# audio_out.net
KiCad netlist of a schematic drawn in Altium Designer
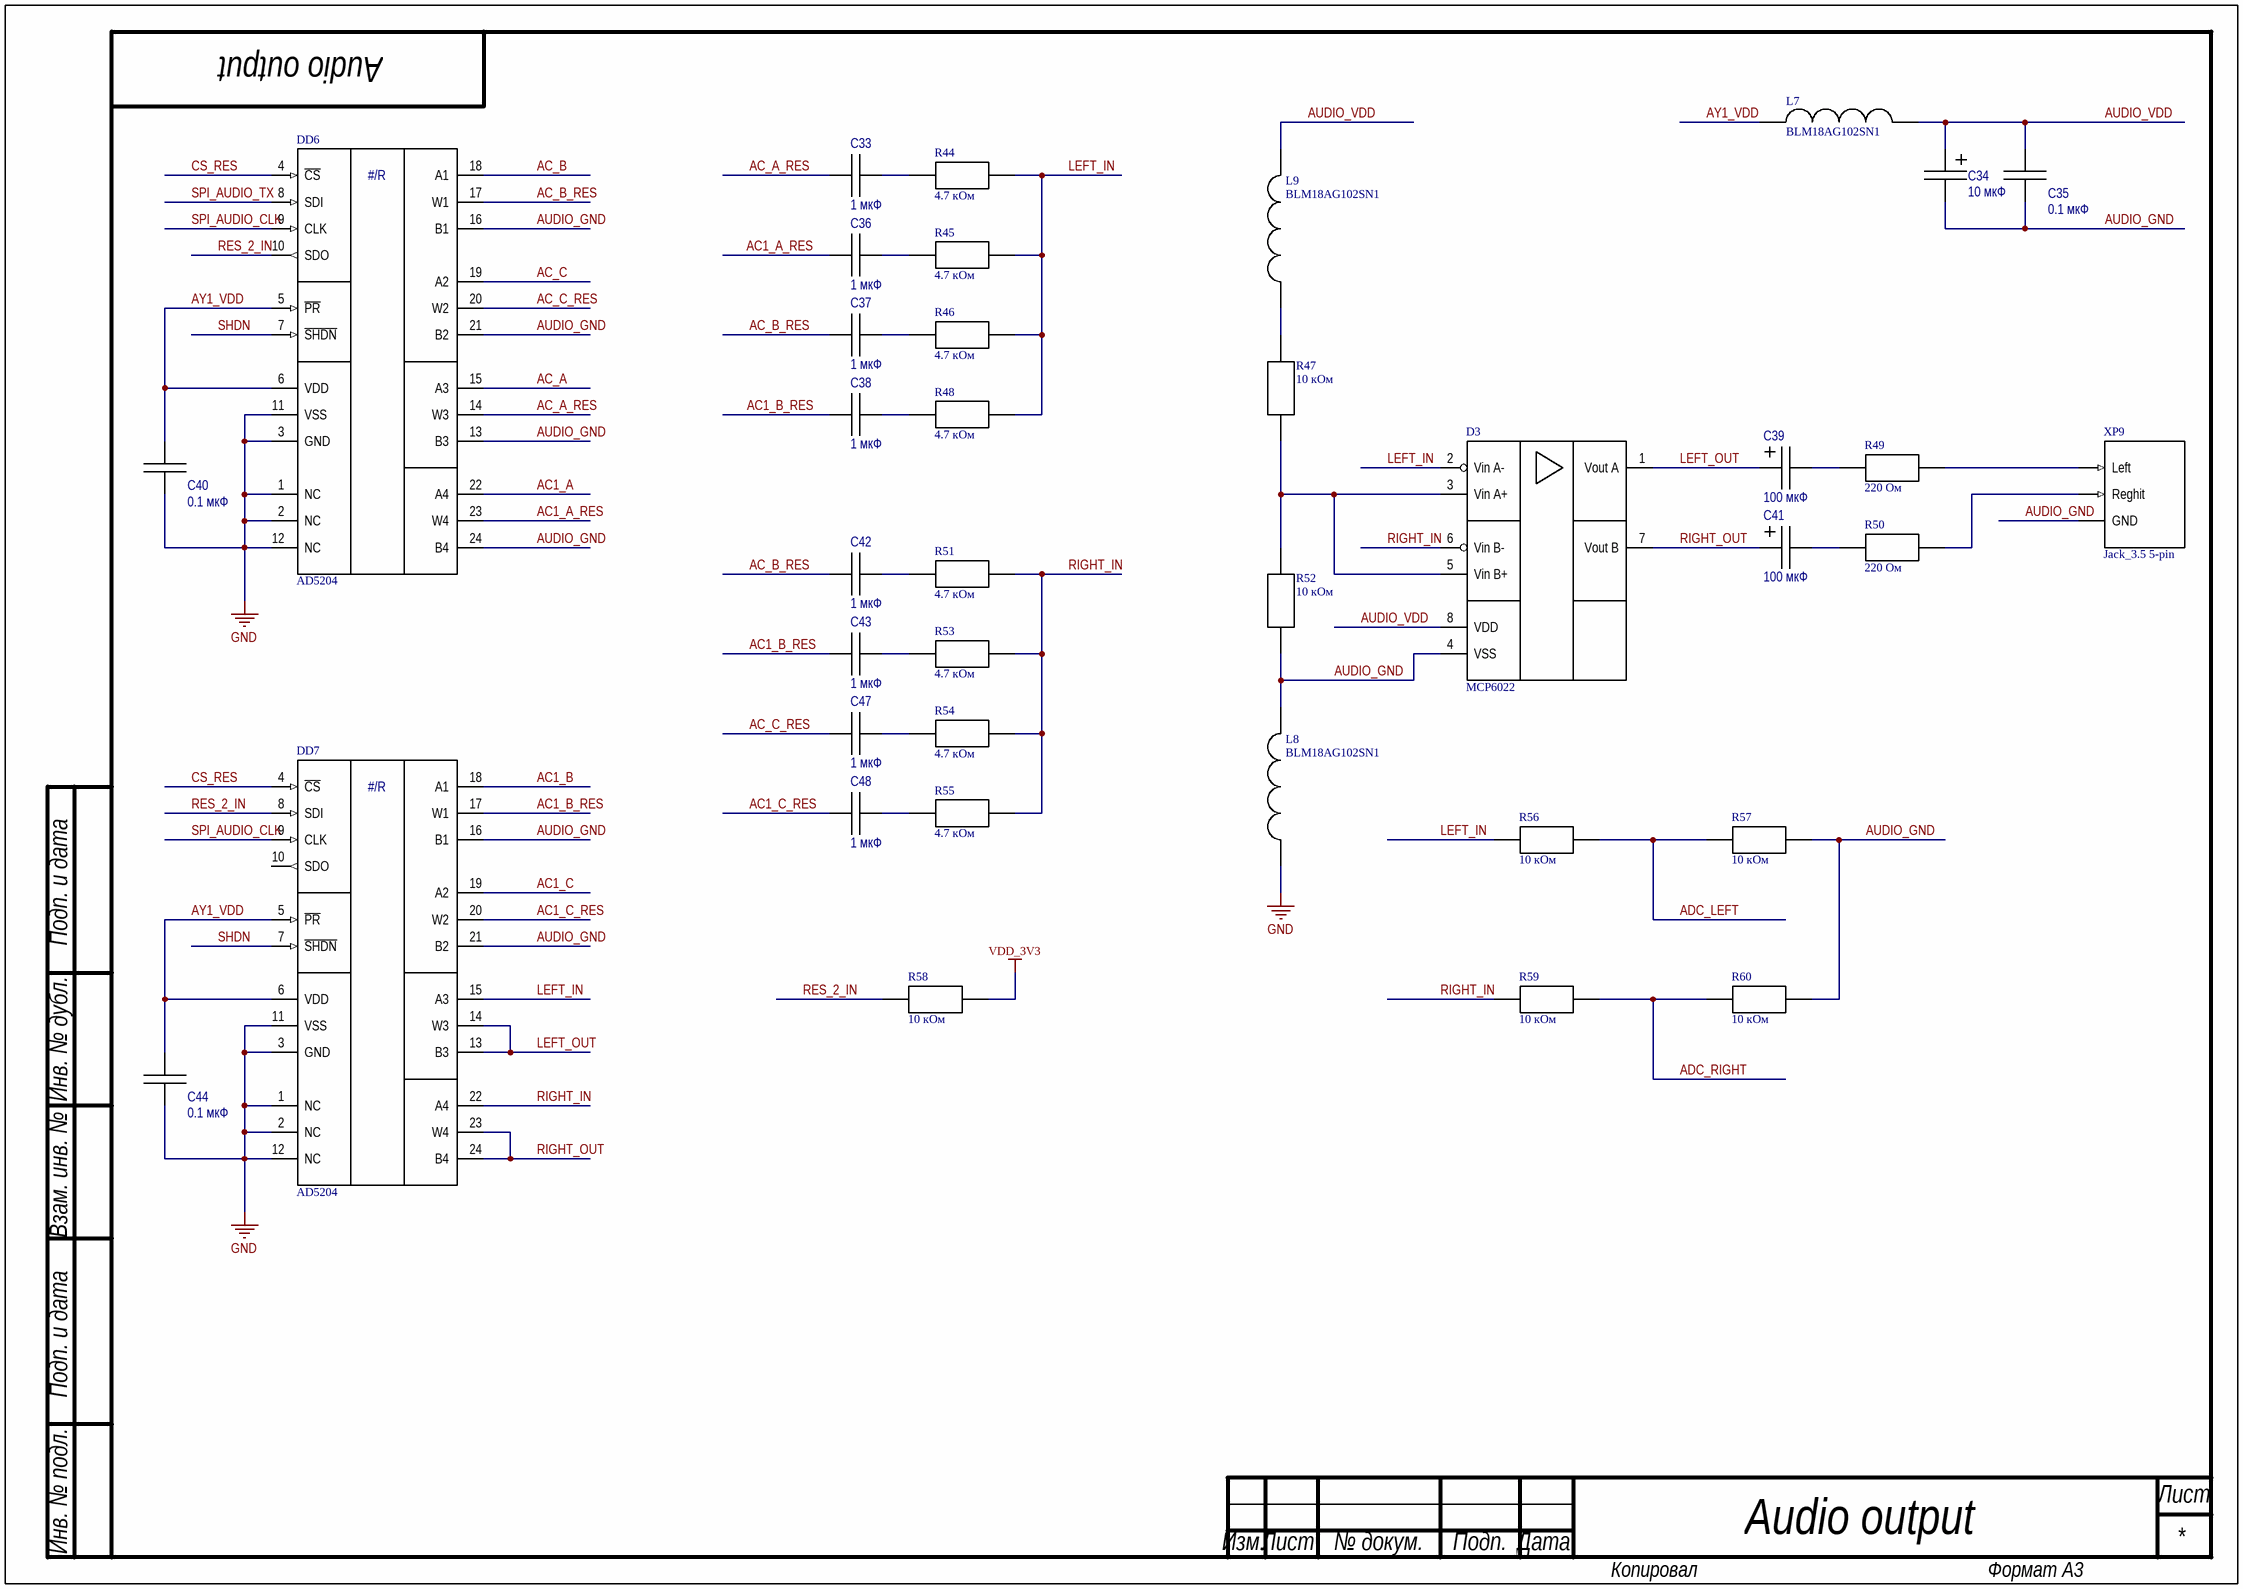
[diagram p0: audio_out.SchDoc]

(export (version "E")
  (design (tool "Eeschema 10.0.6"))
  (components
    (comp (ref "C33")
      (value "1 мкФ")
      (footprint "C 1206")
      (description "SMD Capacitor 1206")
      (fields
        (field (name "TOLERANCE") "/Укажите допуск в процентах/")
        (field (name "MANUFACTURER") "/Укажите компанию-производителя/")
      )
      (libsource (lib "my_lib") (part "CAP 1206"))
    )
    (comp (ref "C34")
      (value "10 мкФ")
      (footprint "C TAN_C")
      (description "SMD Tantalium Capacitor C")
      (fields
        (field (name "TOLERANCE") "/Укажите допуск в процентах/")
        (field (name "MANUFACTURER") "/Укажите компанию-производителя/")
      )
      (libsource (lib "my_lib") (part "CAP TAN_C"))
    )
    (comp (ref "C35")
      (value "0.1 мкФ")
      (footprint "C 1206")
      (description "SMD Capacitor 1206")
      (fields
        (field (name "TOLERANCE") "/Укажите допуск в процентах/")
        (field (name "MANUFACTURER") "/Укажите компанию-производителя/")
      )
      (libsource (lib "my_lib") (part "CAP 1206"))
    )
    (comp (ref "C36")
      (value "1 мкФ")
      (footprint "C 1206")
      (description "SMD Capacitor 1206")
      (fields
        (field (name "TOLERANCE") "/Укажите допуск в процентах/")
        (field (name "MANUFACTURER") "/Укажите компанию-производителя/")
      )
      (libsource (lib "my_lib") (part "CAP 1206"))
    )
    (comp (ref "C37")
      (value "1 мкФ")
      (footprint "C 1206")
      (description "SMD Capacitor 1206")
      (fields
        (field (name "TOLERANCE") "/Укажите допуск в процентах/")
        (field (name "MANUFACTURER") "/Укажите компанию-производителя/")
      )
      (libsource (lib "my_lib") (part "CAP 1206"))
    )
    (comp (ref "C38")
      (value "1 мкФ")
      (footprint "C 1206")
      (description "SMD Capacitor 1206")
      (fields
        (field (name "TOLERANCE") "/Укажите допуск в процентах/")
        (field (name "MANUFACTURER") "/Укажите компанию-производителя/")
      )
      (libsource (lib "my_lib") (part "CAP 1206"))
    )
    (comp (ref "C39")
      (value "100 мкФ")
      (footprint "C TAN_D")
      (description "SMD Tantalium Capacitor D")
      (fields
        (field (name "TOLERANCE") "/Укажите допуск в процентах/")
        (field (name "MANUFACTURER") "/Укажите компанию-производителя/")
      )
      (libsource (lib "my_lib") (part "CAP TAN_D"))
    )
    (comp (ref "C40")
      (value "0.1 мкФ")
      (footprint "C 1206")
      (description "SMD Capacitor 1206")
      (fields
        (field (name "TOLERANCE") "/Укажите допуск в процентах/")
        (field (name "MANUFACTURER") "/Укажите компанию-производителя/")
      )
      (libsource (lib "my_lib") (part "CAP 1206"))
    )
    (comp (ref "C41")
      (value "100 мкФ")
      (footprint "C TAN_D")
      (description "SMD Tantalium Capacitor D")
      (fields
        (field (name "TOLERANCE") "/Укажите допуск в процентах/")
        (field (name "MANUFACTURER") "/Укажите компанию-производителя/")
      )
      (libsource (lib "my_lib") (part "CAP TAN_D"))
    )
    (comp (ref "C42")
      (value "1 мкФ")
      (footprint "C 1206")
      (description "SMD Capacitor 1206")
      (fields
        (field (name "TOLERANCE") "/Укажите допуск в процентах/")
        (field (name "MANUFACTURER") "/Укажите компанию-производителя/")
      )
      (libsource (lib "my_lib") (part "CAP 1206"))
    )
    (comp (ref "C43")
      (value "1 мкФ")
      (footprint "C 1206")
      (description "SMD Capacitor 1206")
      (fields
        (field (name "TOLERANCE") "/Укажите допуск в процентах/")
        (field (name "MANUFACTURER") "/Укажите компанию-производителя/")
      )
      (libsource (lib "my_lib") (part "CAP 1206"))
    )
    (comp (ref "C44")
      (value "0.1 мкФ")
      (footprint "C 1206")
      (description "SMD Capacitor 1206")
      (fields
        (field (name "TOLERANCE") "/Укажите допуск в процентах/")
        (field (name "MANUFACTURER") "/Укажите компанию-производителя/")
      )
      (libsource (lib "my_lib") (part "CAP 1206"))
    )
    (comp (ref "C47")
      (value "1 мкФ")
      (footprint "C 1206")
      (description "SMD Capacitor 1206")
      (fields
        (field (name "TOLERANCE") "/Укажите допуск в процентах/")
        (field (name "MANUFACTURER") "/Укажите компанию-производителя/")
      )
      (libsource (lib "my_lib") (part "CAP 1206"))
    )
    (comp (ref "C48")
      (value "1 мкФ")
      (footprint "C 1206")
      (description "SMD Capacitor 1206")
      (fields
        (field (name "TOLERANCE") "/Укажите допуск в процентах/")
        (field (name "MANUFACTURER") "/Укажите компанию-производителя/")
      )
      (libsource (lib "my_lib") (part "CAP 1206"))
    )
    (comp (ref "D3") (value "MCP6022") (footprint "SOIC-8") (libsource (lib "my_lib") (part "MCP6022")))
    (comp (ref "DD6") (value "AD5204") (footprint "TSSOP-24") (libsource (lib "my_lib") (part "AD5204")))
    (comp (ref "DD7") (value "AD5204") (footprint "TSSOP-24") (libsource (lib "my_lib") (part "AD5204")))
    (comp (ref "L7")
      (value "BLM18AG102SN1")
      (footprint "FB 0603")
      (libsource (lib "my_lib") (part "BLM18AG102SN1"))
    )
    (comp (ref "L8")
      (value "BLM18AG102SN1")
      (footprint "FB 0603")
      (libsource (lib "my_lib") (part "BLM18AG102SN1"))
    )
    (comp (ref "L9")
      (value "BLM18AG102SN1")
      (footprint "FB 0603")
      (libsource (lib "my_lib") (part "BLM18AG102SN1"))
    )
    (comp (ref "R44") (value "4.7 кОм") (footprint "RES 0805") (libsource (lib "my_lib") (part "RES 0805")))
    (comp (ref "R45") (value "4.7 кОм") (footprint "RES 0805") (libsource (lib "my_lib") (part "RES 0805")))
    (comp (ref "R46") (value "4.7 кОм") (footprint "RES 0805") (libsource (lib "my_lib") (part "RES 0805")))
    (comp (ref "R47") (value "10 кОм") (footprint "RES 0805") (libsource (lib "my_lib") (part "RES 0805")))
    (comp (ref "R48") (value "4.7 кОм") (footprint "RES 0805") (libsource (lib "my_lib") (part "RES 0805")))
    (comp (ref "R49") (value "220 Ом") (footprint "RES 0805") (libsource (lib "my_lib") (part "RES 0805")))
    (comp (ref "R50") (value "220 Ом") (footprint "RES 0805") (libsource (lib "my_lib") (part "RES 0805")))
    (comp (ref "R51") (value "4.7 кОм") (footprint "RES 0805") (libsource (lib "my_lib") (part "RES 0805")))
    (comp (ref "R52") (value "10 кОм") (footprint "RES 0805") (libsource (lib "my_lib") (part "RES 0805")))
    (comp (ref "R53") (value "4.7 кОм") (footprint "RES 0805") (libsource (lib "my_lib") (part "RES 0805")))
    (comp (ref "R54") (value "4.7 кОм") (footprint "RES 0805") (libsource (lib "my_lib") (part "RES 0805")))
    (comp (ref "R55") (value "4.7 кОм") (footprint "RES 0805") (libsource (lib "my_lib") (part "RES 0805")))
    (comp (ref "R56") (value "10 кОм") (footprint "RES 0805") (libsource (lib "my_lib") (part "RES 0805")))
    (comp (ref "R57") (value "10 кОм") (footprint "RES 0805") (libsource (lib "my_lib") (part "RES 0805")))
    (comp (ref "R58") (value "10 кОм") (footprint "RES 0805") (libsource (lib "my_lib") (part "RES 0805")))
    (comp (ref "R59") (value "10 кОм") (footprint "RES 0805") (libsource (lib "my_lib") (part "RES 0805")))
    (comp (ref "R60") (value "10 кОм") (footprint "RES 0805") (libsource (lib "my_lib") (part "RES 0805")))
    (comp (ref "XP9")
      (value "Jack_3.5 5-pin")
      (footprint "JACK 3.5  female")
      (libsource (lib "my_lib") (part "Jack_3.5 5-pin"))
    )
  )
  (nets
    (net (code "1") (name "/AC1_A") (class "Default")
      (node (ref "DD6") (pin "22") (pinfunction "A4_22") (pintype "passive"))
    )
    (net (code "2") (name "/AC1_A_RES") (class "Default")
      (node (ref "C36") (pin "1") (pinfunction "1_1") (pintype "passive"))
      (node (ref "DD6") (pin "23") (pinfunction "W4_23") (pintype "passive"))
    )
    (net (code "3") (name "/AC1_B") (class "Default")
      (node (ref "DD7") (pin "18") (pinfunction "A1_18") (pintype "passive"))
    )
    (net (code "4") (name "/AC1_B_RES") (class "Default")
      (node (ref "C38") (pin "1") (pinfunction "1_1") (pintype "passive"))
      (node (ref "C43") (pin "1") (pinfunction "1_1") (pintype "passive"))
      (node (ref "DD7") (pin "17") (pinfunction "W1_17") (pintype "passive"))
    )
    (net (code "5") (name "/AC1_C") (class "Default")
      (node (ref "DD7") (pin "19") (pinfunction "A2_19") (pintype "passive"))
    )
    (net (code "6") (name "/AC1_C_RES") (class "Default")
      (node (ref "C48") (pin "1") (pinfunction "1_1") (pintype "passive"))
      (node (ref "DD7") (pin "20") (pinfunction "W2_20") (pintype "passive"))
    )
    (net (code "7") (name "/AC_A") (class "Default")
      (node (ref "DD6") (pin "15") (pinfunction "A3_15") (pintype "passive"))
    )
    (net (code "8") (name "/AC_A_RES") (class "Default")
      (node (ref "C33") (pin "1") (pinfunction "1_1") (pintype "passive"))
      (node (ref "DD6") (pin "14") (pinfunction "W3_14") (pintype "passive"))
    )
    (net (code "9") (name "/AC_B") (class "Default")
      (node (ref "DD6") (pin "18") (pinfunction "A1_18") (pintype "passive"))
    )
    (net (code "10") (name "/AC_B_RES") (class "Default")
      (node (ref "C37") (pin "1") (pinfunction "1_1") (pintype "passive"))
      (node (ref "C42") (pin "1") (pinfunction "1_1") (pintype "passive"))
      (node (ref "DD6") (pin "17") (pinfunction "W1_17") (pintype "passive"))
    )
    (net (code "11") (name "/AC_C") (class "Default")
      (node (ref "DD6") (pin "19") (pinfunction "A2_19") (pintype "passive"))
    )
    (net (code "12") (name "/AC_C_RES") (class "Default")
      (node (ref "C47") (pin "1") (pinfunction "1_1") (pintype "passive"))
      (node (ref "DD6") (pin "20") (pinfunction "W2_20") (pintype "passive"))
    )
    (net (code "13") (name "/ADC_LEFT") (class "Default")
      (node (ref "R56") (pin "1") (pinfunction "1_1") (pintype "passive"))
      (node (ref "R57") (pin "2") (pinfunction "2_2") (pintype "passive"))
    )
    (net (code "14") (name "/ADC_RIGHT") (class "Default")
      (node (ref "R59") (pin "1") (pinfunction "1_1") (pintype "passive"))
      (node (ref "R60") (pin "2") (pinfunction "2_2") (pintype "passive"))
    )
    (net (code "15") (name "/AUDIO_GND") (class "Default")
      (node (ref "C34") (pin "2") (pinfunction "2_2") (pintype "passive"))
      (node (ref "C35") (pin "2") (pinfunction "2_2") (pintype "passive"))
      (node (ref "D3") (pin "4") (pinfunction "VSS_4") (pintype "power_in"))
      (node (ref "DD6") (pin "13") (pinfunction "B3_13") (pintype "passive"))
      (node (ref "DD6") (pin "16") (pinfunction "B1_16") (pintype "passive"))
      (node (ref "DD6") (pin "21") (pinfunction "B2_21") (pintype "passive"))
      (node (ref "DD6") (pin "24") (pinfunction "B4_24") (pintype "passive"))
      (node (ref "DD7") (pin "16") (pinfunction "B1_16") (pintype "passive"))
      (node (ref "DD7") (pin "21") (pinfunction "B2_21") (pintype "passive"))
      (node (ref "L8") (pin "2") (pinfunction "2_2") (pintype "passive"))
      (node (ref "R52") (pin "1") (pinfunction "1_1") (pintype "passive"))
      (node (ref "R57") (pin "1") (pinfunction "1_1") (pintype "passive"))
      (node (ref "R60") (pin "1") (pinfunction "1_1") (pintype "passive"))
      (node (ref "XP9") (pin "G") (pinfunction "GND_G") (pintype "power_in"))
    )
    (net (code "16") (name "/AUDIO_VDD") (class "Default")
      (node (ref "C34") (pin "1") (pinfunction "1_1") (pintype "passive"))
      (node (ref "C35") (pin "1") (pinfunction "1_1") (pintype "passive"))
      (node (ref "D3") (pin "8") (pinfunction "VDD_8") (pintype "power_in"))
      (node (ref "L7") (pin "2") (pinfunction "2_2") (pintype "passive"))
      (node (ref "L9") (pin "2") (pinfunction "2_2") (pintype "passive"))
    )
    (net (code "17") (name "/AY1_VDD") (class "Default")
      (node (ref "C40") (pin "1") (pinfunction "1_1") (pintype "passive"))
      (node (ref "C44") (pin "1") (pinfunction "1_1") (pintype "passive"))
      (node (ref "DD6") (pin "5") (pinfunction "~{PR}_5") (pintype "input"))
      (node (ref "DD6") (pin "6") (pinfunction "VDD_6") (pintype "power_in"))
      (node (ref "DD7") (pin "5") (pinfunction "~{PR}_5") (pintype "input"))
      (node (ref "DD7") (pin "6") (pinfunction "VDD_6") (pintype "power_in"))
      (node (ref "L7") (pin "1") (pinfunction "1_1") (pintype "passive"))
    )
    (net (code "18") (name "/CS_RES") (class "Default")
      (node (ref "DD6") (pin "4") (pinfunction "~{CS}_4") (pintype "input"))
      (node (ref "DD7") (pin "4") (pinfunction "~{CS}_4") (pintype "input"))
    )
    (net (code "19") (name "/LEFT_IN") (class "Default")
      (node (ref "D3") (pin "2") (pinfunction "Vin_A-_2") (pintype "passive"))
      (node (ref "DD7") (pin "15") (pinfunction "A3_15") (pintype "passive"))
      (node (ref "R44") (pin "2") (pinfunction "2_2") (pintype "passive"))
      (node (ref "R45") (pin "2") (pinfunction "2_2") (pintype "passive"))
      (node (ref "R46") (pin "2") (pinfunction "2_2") (pintype "passive"))
      (node (ref "R48") (pin "2") (pinfunction "2_2") (pintype "passive"))
      (node (ref "R56") (pin "2") (pinfunction "2_2") (pintype "passive"))
    )
    (net (code "20") (name "/LEFT_OUT") (class "Default")
      (node (ref "C39") (pin "1") (pinfunction "1_1") (pintype "passive"))
      (node (ref "D3") (pin "1") (pinfunction "Vout_A_1") (pintype "passive"))
      (node (ref "DD7") (pin "13") (pinfunction "B3_13") (pintype "passive"))
      (node (ref "DD7") (pin "14") (pinfunction "W3_14") (pintype "passive"))
    )
    (net (code "21") (name "/RES_2_IN") (class "Default")
      (node (ref "DD6") (pin "10") (pinfunction "SDO_10") (pintype "output"))
      (node (ref "DD7") (pin "8") (pinfunction "SDI_8") (pintype "input"))
      (node (ref "R58") (pin "1") (pinfunction "1_1") (pintype "passive"))
    )
    (net (code "22") (name "/RIGHT_IN") (class "Default")
      (node (ref "D3") (pin "6") (pinfunction "Vin_B-_6") (pintype "passive"))
      (node (ref "DD7") (pin "22") (pinfunction "A4_22") (pintype "passive"))
      (node (ref "R51") (pin "2") (pinfunction "2_2") (pintype "passive"))
      (node (ref "R53") (pin "2") (pinfunction "2_2") (pintype "passive"))
      (node (ref "R54") (pin "2") (pinfunction "2_2") (pintype "passive"))
      (node (ref "R55") (pin "2") (pinfunction "2_2") (pintype "passive"))
      (node (ref "R59") (pin "2") (pinfunction "2_2") (pintype "passive"))
    )
    (net (code "23") (name "/RIGHT_OUT") (class "Default")
      (node (ref "C41") (pin "1") (pinfunction "1_1") (pintype "passive"))
      (node (ref "D3") (pin "7") (pinfunction "Vout_B_7") (pintype "passive"))
      (node (ref "DD7") (pin "23") (pinfunction "W4_23") (pintype "passive"))
      (node (ref "DD7") (pin "24") (pinfunction "B4_24") (pintype "passive"))
    )
    (net (code "24") (name "/SHDN") (class "Default")
      (node (ref "DD6") (pin "7") (pinfunction "~{SHDN}_7") (pintype "input"))
      (node (ref "DD7") (pin "7") (pinfunction "~{SHDN}_7") (pintype "input"))
    )
    (net (code "25") (name "/SPI_AUDIO_CLK") (class "Default")
      (node (ref "DD6") (pin "9") (pinfunction "CLK_9") (pintype "input"))
      (node (ref "DD7") (pin "9") (pinfunction "CLK_9") (pintype "input"))
    )
    (net (code "26") (name "/SPI_AUDIO_TX") (class "Default")
      (node (ref "DD6") (pin "8") (pinfunction "SDI_8") (pintype "input"))
    )
    (net (code "27") (name "GND") (class "Default")
      (node (ref "C40") (pin "2") (pinfunction "2_2") (pintype "passive"))
      (node (ref "C44") (pin "2") (pinfunction "2_2") (pintype "passive"))
      (node (ref "DD6") (pin "1") (pinfunction "NC_1") (pintype "passive"))
      (node (ref "DD6") (pin "11") (pinfunction "VSS_11") (pintype "power_in"))
      (node (ref "DD6") (pin "12") (pinfunction "NC_12") (pintype "passive"))
      (node (ref "DD6") (pin "2") (pinfunction "NC_2") (pintype "passive"))
      (node (ref "DD6") (pin "3") (pinfunction "GND_3") (pintype "power_in"))
      (node (ref "DD7") (pin "1") (pinfunction "NC_1") (pintype "passive"))
      (node (ref "DD7") (pin "11") (pinfunction "VSS_11") (pintype "power_in"))
      (node (ref "DD7") (pin "12") (pinfunction "NC_12") (pintype "passive"))
      (node (ref "DD7") (pin "2") (pinfunction "NC_2") (pintype "passive"))
      (node (ref "DD7") (pin "3") (pinfunction "GND_3") (pintype "power_in"))
      (node (ref "L8") (pin "1") (pinfunction "1_1") (pintype "passive"))
    )
    (net (code "28") (name "Net-(C33-Pad2)") (class "Default")
      (node (ref "C33") (pin "2") (pinfunction "2_2") (pintype "passive"))
      (node (ref "R44") (pin "1") (pinfunction "1_1") (pintype "passive"))
    )
    (net (code "29") (name "Net-(C36-Pad2)") (class "Default")
      (node (ref "C36") (pin "2") (pinfunction "2_2") (pintype "passive"))
      (node (ref "R45") (pin "1") (pinfunction "1_1") (pintype "passive"))
    )
    (net (code "30") (name "Net-(C37-Pad2)") (class "Default")
      (node (ref "C37") (pin "2") (pinfunction "2_2") (pintype "passive"))
      (node (ref "R46") (pin "1") (pinfunction "1_1") (pintype "passive"))
    )
    (net (code "31") (name "Net-(C38-Pad2)") (class "Default")
      (node (ref "C38") (pin "2") (pinfunction "2_2") (pintype "passive"))
      (node (ref "R48") (pin "1") (pinfunction "1_1") (pintype "passive"))
    )
    (net (code "32") (name "Net-(C39-Pad2)") (class "Default")
      (node (ref "C39") (pin "2") (pinfunction "2_2") (pintype "passive"))
      (node (ref "R49") (pin "1") (pinfunction "1_1") (pintype "passive"))
    )
    (net (code "33") (name "Net-(C41-Pad2)") (class "Default")
      (node (ref "C41") (pin "2") (pinfunction "2_2") (pintype "passive"))
      (node (ref "R50") (pin "1") (pinfunction "1_1") (pintype "passive"))
    )
    (net (code "34") (name "Net-(C42-Pad2)") (class "Default")
      (node (ref "C42") (pin "2") (pinfunction "2_2") (pintype "passive"))
      (node (ref "R51") (pin "1") (pinfunction "1_1") (pintype "passive"))
    )
    (net (code "35") (name "Net-(C43-Pad2)") (class "Default")
      (node (ref "C43") (pin "2") (pinfunction "2_2") (pintype "passive"))
      (node (ref "R53") (pin "1") (pinfunction "1_1") (pintype "passive"))
    )
    (net (code "36") (name "Net-(C47-Pad2)") (class "Default")
      (node (ref "C47") (pin "2") (pinfunction "2_2") (pintype "passive"))
      (node (ref "R54") (pin "1") (pinfunction "1_1") (pintype "passive"))
    )
    (net (code "37") (name "Net-(C48-Pad2)") (class "Default")
      (node (ref "C48") (pin "2") (pinfunction "2_2") (pintype "passive"))
      (node (ref "R55") (pin "1") (pinfunction "1_1") (pintype "passive"))
    )
    (net (code "38") (name "Net-(D3-Vin_A+)") (class "Default")
      (node (ref "D3") (pin "3") (pinfunction "Vin_A+_3") (pintype "passive"))
      (node (ref "D3") (pin "5") (pinfunction "Vin_B+_5") (pintype "passive"))
      (node (ref "R47") (pin "1") (pinfunction "1_1") (pintype "passive"))
      (node (ref "R52") (pin "2") (pinfunction "2_2") (pintype "passive"))
    )
    (net (code "39") (name "Net-(L9-Pad1)") (class "Default")
      (node (ref "L9") (pin "1") (pinfunction "1_1") (pintype "passive"))
      (node (ref "R47") (pin "2") (pinfunction "2_2") (pintype "passive"))
    )
    (net (code "40") (name "Net-(XP9-Left)") (class "Default")
      (node (ref "R49") (pin "2") (pinfunction "2_2") (pintype "passive"))
      (node (ref "XP9") (pin "L") (pinfunction "Left_L") (pintype "input"))
    )
    (net (code "41") (name "Net-(XP9-Reghit)") (class "Default")
      (node (ref "R50") (pin "2") (pinfunction "2_2") (pintype "passive"))
      (node (ref "XP9") (pin "R") (pinfunction "Reghit_R") (pintype "input"))
    )
    (net (code "42") (name "VDD_3V3") (class "Default")
      (node (ref "R58") (pin "2") (pinfunction "2_2") (pintype "passive"))
    )
    (net (code "43") (name "unconnected-(DD7-SDO-Pad10)") (class "Default")
      (node (ref "DD7") (pin "10") (pinfunction "SDO_10") (pintype "output"))
    )
  )
)
